# LCD-Connecteur-ST7920.net
KiCad netlist of a schematic drawn in Altium Designer
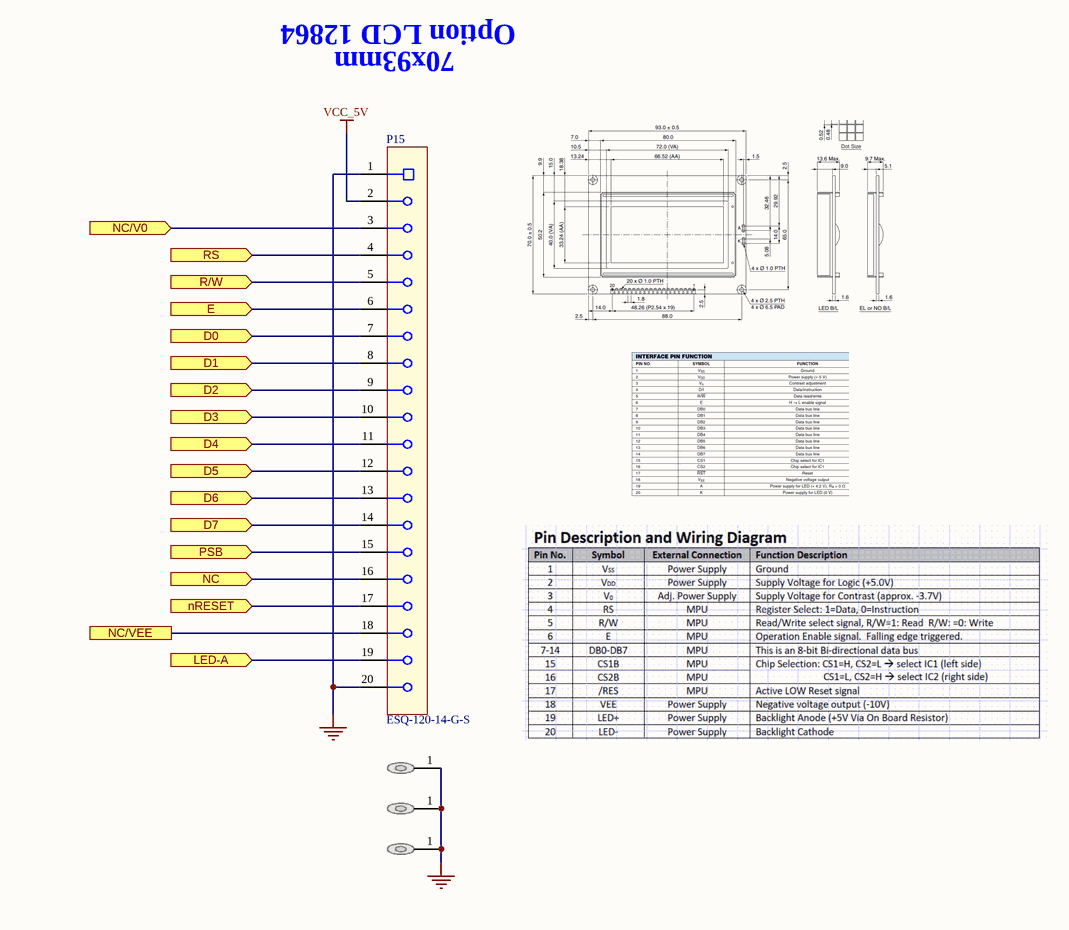
[diagram p0: LCD-Connecteur-ST7920.SchDoc]

(export (version "E")
  (design (tool "Eeschema 10.0.6"))
  (components
    (comp (ref "MH9")
      (value "DNP")
      (footprint "MP_M-Hole_M2.5x0.45mm_LOOSE-FIT")
      (description "Mounting Hole 2.5mm w/ Flat Washer")
      (libsource (lib "TEP_243-AltiumLIB-Conn-TP-MH") (part "MH-2.5MM"))
    )
    (comp (ref "MH10")
      (value "DNP")
      (footprint "MP_M-Hole_M2.5x0.45mm_LOOSE-FIT")
      (description "Mounting Hole 2.5mm w/ Flat Washer")
      (libsource (lib "TEP_243-AltiumLIB-Conn-TP-MH") (part "MH-2.5MM"))
    )
    (comp (ref "MH11")
      (value "DNP")
      (footprint "MP_M-Hole_M2.5x0.45mm_LOOSE-FIT")
      (description "Mounting Hole 2.5mm w/ Flat Washer")
      (libsource (lib "TEP_243-AltiumLIB-Conn-TP-MH") (part "MH-2.5MM"))
    )
    (comp (ref "P15")
      (value "ESQ-120-14-G-S")
      (footprint "CONN-SKT-20POS-100MIL")
      (description "CONN SOCKET 20POS 2.54MM")
      (libsource (lib "TEP_243-AltiumLIB-Conn-TP-MH") (part "CONN-100MIL-SKT-01X20"))
    )
  )
  (nets
    (net (code "1") (name "/D0") (class "Default")
      (node (ref "P15") (pin "7") (pinfunction "7_7") (pintype "passive"))
    )
    (net (code "2") (name "/D1") (class "Default")
      (node (ref "P15") (pin "8") (pinfunction "8_8") (pintype "passive"))
    )
    (net (code "3") (name "/D2") (class "Default")
      (node (ref "P15") (pin "9") (pinfunction "9_9") (pintype "passive"))
    )
    (net (code "4") (name "/D3") (class "Default")
      (node (ref "P15") (pin "10") (pinfunction "10_10") (pintype "passive"))
    )
    (net (code "5") (name "/D4") (class "Default")
      (node (ref "P15") (pin "11") (pinfunction "11_11") (pintype "passive"))
    )
    (net (code "6") (name "/D5") (class "Default")
      (node (ref "P15") (pin "12") (pinfunction "12_12") (pintype "passive"))
    )
    (net (code "7") (name "/D6") (class "Default")
      (node (ref "P15") (pin "13") (pinfunction "13_13") (pintype "passive"))
    )
    (net (code "8") (name "/D7") (class "Default")
      (node (ref "P15") (pin "14") (pinfunction "14_14") (pintype "passive"))
    )
    (net (code "9") (name "/E") (class "Default")
      (node (ref "P15") (pin "6") (pinfunction "6_6") (pintype "passive"))
    )
    (net (code "10") (name "/LED-A") (class "Default")
      (node (ref "P15") (pin "19") (pinfunction "19_19") (pintype "passive"))
    )
    (net (code "11") (name "/NC") (class "Default")
      (node (ref "P15") (pin "16") (pinfunction "16_16") (pintype "passive"))
    )
    (net (code "12") (name "/NC{slash}V0") (class "Default")
      (node (ref "P15") (pin "3") (pinfunction "3_3") (pintype "passive"))
    )
    (net (code "13") (name "/NC{slash}VEE") (class "Default")
      (node (ref "P15") (pin "18") (pinfunction "18_18") (pintype "passive"))
    )
    (net (code "14") (name "/PSB") (class "Default")
      (node (ref "P15") (pin "15") (pinfunction "15_15") (pintype "passive"))
    )
    (net (code "15") (name "/RS") (class "Default")
      (node (ref "P15") (pin "4") (pinfunction "4_4") (pintype "passive"))
    )
    (net (code "16") (name "/R{slash}W") (class "Default")
      (node (ref "P15") (pin "5") (pinfunction "5_5") (pintype "passive"))
    )
    (net (code "17") (name "/nRESET") (class "Default")
      (node (ref "P15") (pin "17") (pinfunction "17_17") (pintype "passive"))
    )
    (net (code "18") (name "GND") (class "Default")
      (node (ref "MH10") (pin "1") (pinfunction "1_1") (pintype "power_in"))
      (node (ref "MH11") (pin "1") (pinfunction "1_1") (pintype "power_in"))
      (node (ref "MH9") (pin "1") (pinfunction "1_1") (pintype "power_in"))
      (node (ref "P15") (pin "1") (pinfunction "1_1") (pintype "passive"))
      (node (ref "P15") (pin "20") (pinfunction "20_20") (pintype "passive"))
    )
    (net (code "19") (name "VCC_5V") (class "Default")
      (node (ref "P15") (pin "2") (pinfunction "2_2") (pintype "passive"))
    )
  )
)
